# MRCS-Morse-Code-Buzzer.net
KiCad netlist of a schematic drawn in EAGLE
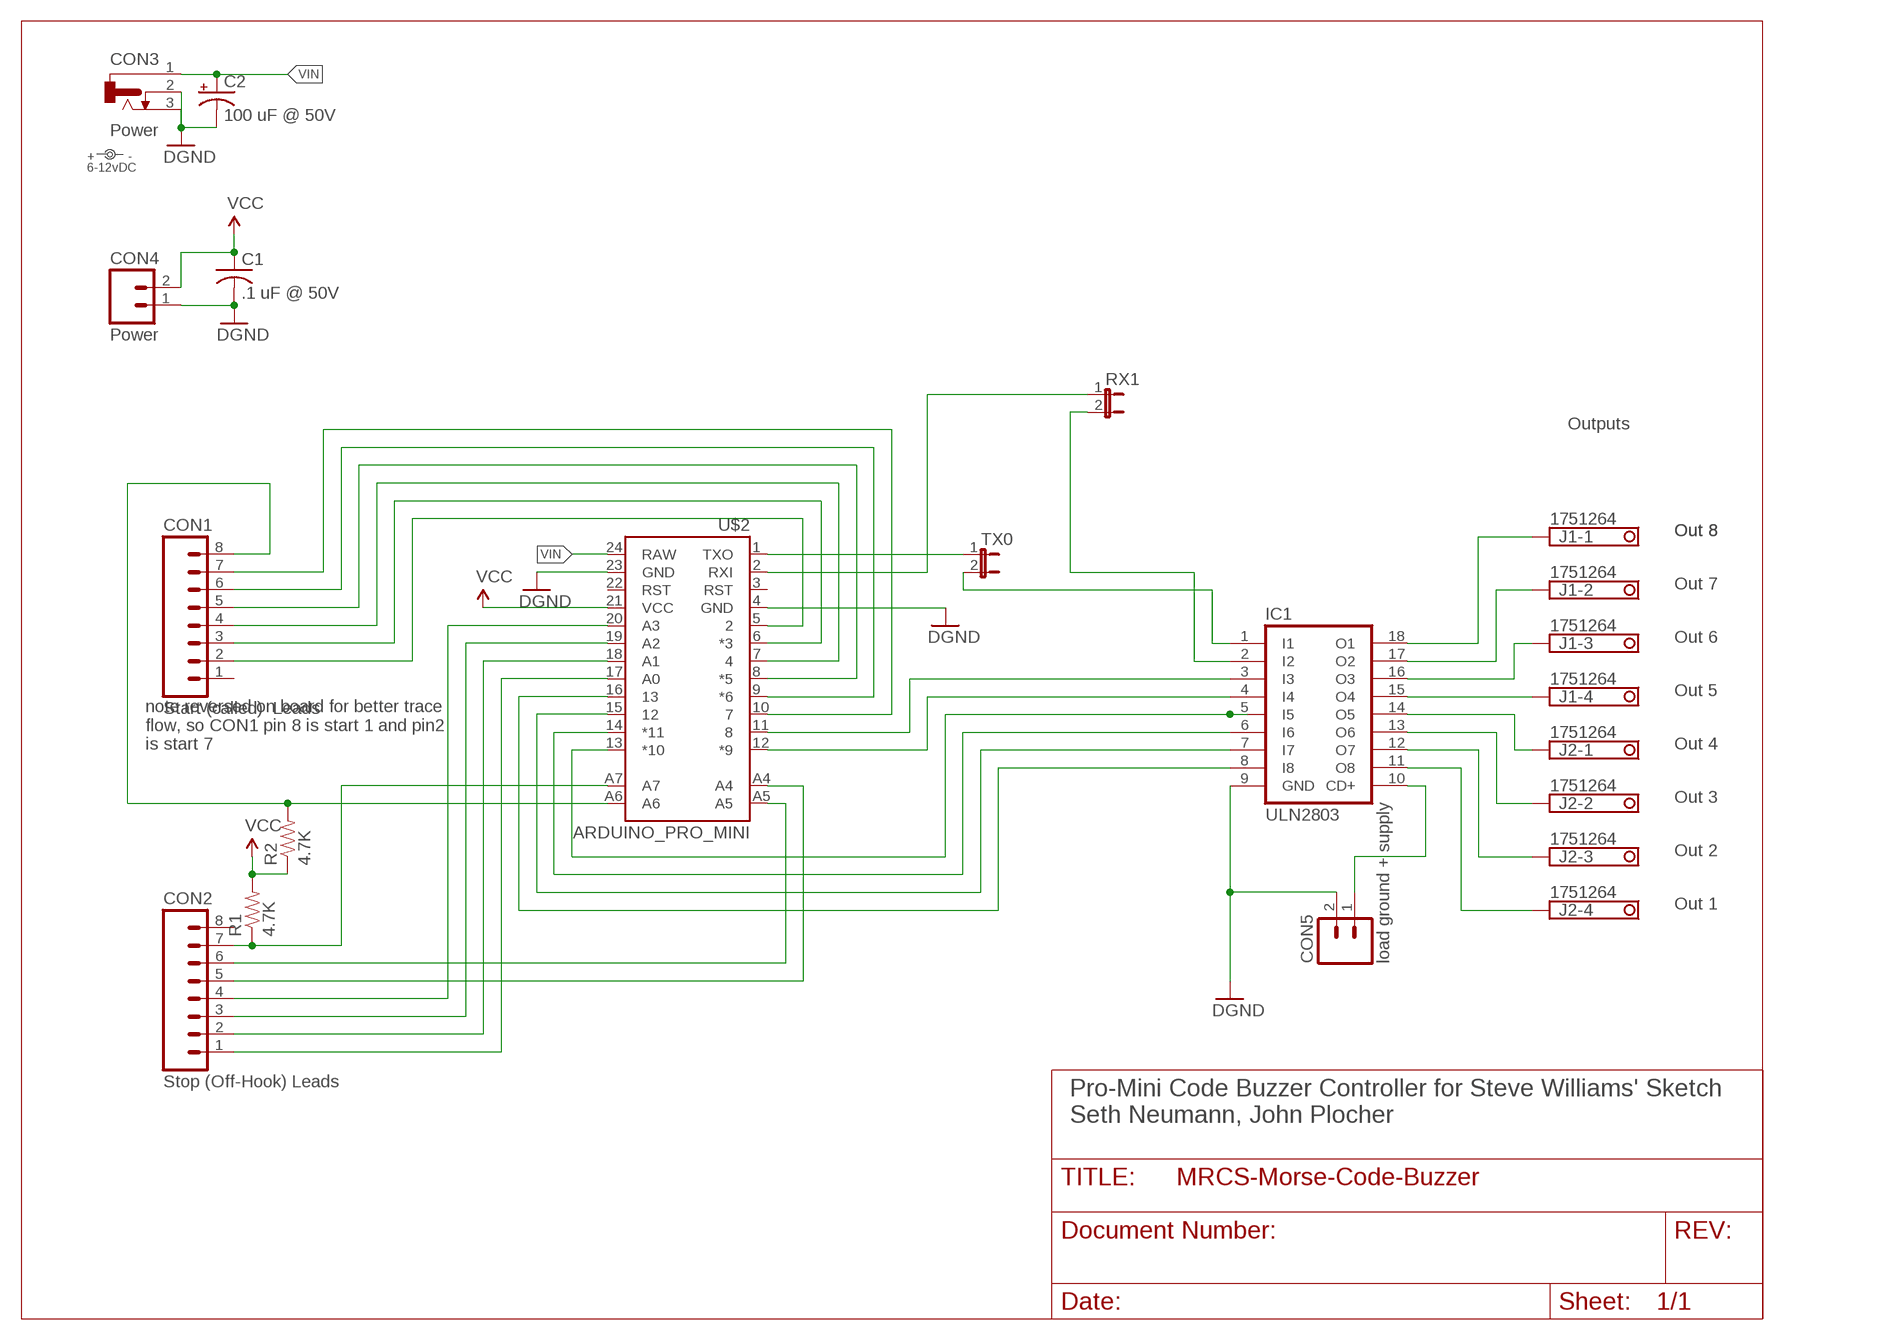
[diagram p0: schematic, sheet 1]

(export (version "E")
  (design (tool "Eeschema 10.0.6"))
  (components
    (comp (ref "C1")
      (value ".1 uF @ 50V")
      (footprint "eagle-import:C025-030X050")
      (libsource (lib "eagle-import") (part "C-US025-030X050"))
    )
    (comp (ref "C2")
      (value "100 uF @ 50V")
      (footprint "eagle-import:E3.5-10")
      (libsource (lib "eagle-import") (part "CAP-POLPTH-3.5MM"))
    )
    (comp (ref "CON1")
      (value "Start (called) Leads")
      (footprint "eagle-import:1X08_LOCK")
      (libsource (lib "eagle-import") (part "CONNECTOR-M08LOCK"))
    )
    (comp (ref "CON2")
      (value "Stop (Off-Hook) Leads")
      (footprint "eagle-import:1X08_LOCK")
      (libsource (lib "eagle-import") (part "CONNECTOR-M08LOCK"))
    )
    (comp (ref "CON3")
      (value "Power")
      (footprint "eagle-import:DCJ0202")
      (libsource (lib "eagle-import") (part "CONNECTOR-DC-POWER-RA"))
    )
    (comp (ref "CON4")
      (value "Power")
      (footprint "eagle-import:MSTB2")
      (libsource (lib "eagle-import") (part "CONNECTOR-M02508-LOCK"))
    )
    (comp (ref "CON5")
      (value "load ground + supply")
      (footprint "eagle-import:MSTB2")
      (libsource (lib "eagle-import") (part "CONNECTOR-M02508-LOCK"))
    )
    (comp (ref "IC1")
      (value "ULN2803")
      (footprint "eagle-import:DIL18")
      (libsource (lib "eagle-import") (part "ULN2803A"))
    )
    (comp (ref "J1")
      (value "1751264")
      (footprint "eagle-import:1751264")
      (libsource (lib "eagle-import") (part "1751264"))
    )
    (comp (ref "J2")
      (value "1751264")
      (footprint "eagle-import:1751264")
      (libsource (lib "eagle-import") (part "1751264"))
    )
    (comp (ref "R1")
      (value "4.7K")
      (footprint "eagle-import:AXIAL-0.4-RES")
      (libsource (lib "eagle-import") (part "RPTH04"))
    )
    (comp (ref "R2")
      (value "4.7K")
      (footprint "eagle-import:AXIAL-0.4-RES")
      (libsource (lib "eagle-import") (part "RPTH04"))
    )
    (comp (ref "RX1")
      (value "JUMPER-2PTH")
      (footprint "eagle-import:1X02")
      (libsource (lib "eagle-import") (part "JUMPER-2PTH"))
    )
    (comp (ref "TX0")
      (value "JUMPER-2PTH")
      (footprint "eagle-import:1X02")
      (libsource (lib "eagle-import") (part "JUMPER-2PTH"))
    )
    (comp (ref "U$2")
      (value "ARDUINO_PRO_MINI")
      (footprint "eagle-import:ARDUINO_PRO_MINI")
      (libsource (lib "eagle-import") (part "ARDUINO_PRO_MINI"))
    )
    (comp (ref "U$4")
      (value "6-12vDC")
      (footprint "eagle-import:PWR_LABEL")
      (libsource (lib "eagle-import") (part "DOC-POWER_LABEL"))
    )
  )
  (nets
    (net (code "1") (name "DGND") (class "Default")
      (node (ref "C1") (pin "2") (pinfunction "2_2") (pintype "passive"))
      (node (ref "C2") (pin "-") (pinfunction "-_-") (pintype "passive"))
      (node (ref "CON3") (pin "2") (pinfunction "2_2") (pintype "passive"))
      (node (ref "CON3") (pin "3") (pinfunction "3_3") (pintype "passive"))
      (node (ref "CON4") (pin "1") (pinfunction "A_1") (pintype "passive"))
      (node (ref "CON5") (pin "2") (pinfunction "B_2") (pintype "passive"))
      (node (ref "IC1") (pin "9") (pinfunction "GND_9") (pintype "power_in"))
      (node (ref "U$2") (pin "23") (pinfunction "GND_23") (pintype "bidirectional"))
      (node (ref "U$2") (pin "4") (pinfunction "GND_4") (pintype "bidirectional"))
    )
    (net (code "2") (name "Net-(CON2-Pad5)") (class "Default")
      (node (ref "CON2") (pin "5") (pinfunction "5_5") (pintype "passive"))
      (node (ref "U$2") (pin "A4") (pinfunction "A4_A4") (pintype "bidirectional"))
    )
    (net (code "3") (name "Net-(CON2-Pad6)") (class "Default")
      (node (ref "CON2") (pin "6") (pinfunction "6_6") (pintype "passive"))
      (node (ref "U$2") (pin "A5") (pinfunction "A5_A5") (pintype "bidirectional"))
    )
    (net (code "4") (name "Net-(CON5-A)") (class "Default")
      (node (ref "CON5") (pin "1") (pinfunction "A_1") (pintype "passive"))
      (node (ref "IC1") (pin "10") (pinfunction "CD+_10") (pintype "passive"))
    )
    (net (code "5") (name "Net-(IC1-I1)") (class "Default")
      (node (ref "IC1") (pin "1") (pinfunction "I1_1") (pintype "input"))
      (node (ref "TX0") (pin "2") (pinfunction "2_2") (pintype "passive"))
    )
    (net (code "6") (name "Net-(IC1-I2)") (class "Default")
      (node (ref "IC1") (pin "2") (pinfunction "I2_2") (pintype "input"))
      (node (ref "RX1") (pin "2") (pinfunction "2_2") (pintype "passive"))
    )
    (net (code "7") (name "Net-(IC1-I3)") (class "Default")
      (node (ref "IC1") (pin "3") (pinfunction "I3_3") (pintype "input"))
      (node (ref "U$2") (pin "11") (pinfunction "8_11") (pintype "bidirectional"))
    )
    (net (code "8") (name "Net-(IC1-I4)") (class "Default")
      (node (ref "IC1") (pin "4") (pinfunction "I4_4") (pintype "input"))
      (node (ref "U$2") (pin "12") (pinfunction "*9_12") (pintype "bidirectional"))
    )
    (net (code "9") (name "Net-(IC1-I5)") (class "Default")
      (node (ref "IC1") (pin "5") (pinfunction "I5_5") (pintype "input"))
      (node (ref "U$2") (pin "13") (pinfunction "*10_13") (pintype "bidirectional"))
    )
    (net (code "10") (name "Net-(IC1-I6)") (class "Default")
      (node (ref "IC1") (pin "6") (pinfunction "I6_6") (pintype "input"))
      (node (ref "U$2") (pin "14") (pinfunction "*11_14") (pintype "bidirectional"))
    )
    (net (code "11") (name "Net-(IC1-I7)") (class "Default")
      (node (ref "IC1") (pin "7") (pinfunction "I7_7") (pintype "input"))
      (node (ref "U$2") (pin "15") (pinfunction "12_15") (pintype "bidirectional"))
    )
    (net (code "12") (name "Net-(IC1-I8)") (class "Default")
      (node (ref "IC1") (pin "8") (pinfunction "I8_8") (pintype "input"))
      (node (ref "U$2") (pin "16") (pinfunction "13_16") (pintype "bidirectional"))
    )
    (net (code "13") (name "Net-(IC1-O1)") (class "Default")
      (node (ref "IC1") (pin "18") (pinfunction "O1_18") (pintype "open_collector"))
      (node (ref "J1") (pin "1") (pinfunction "K_1") (pintype "passive"))
    )
    (net (code "14") (name "Net-(IC1-O2)") (class "Default")
      (node (ref "IC1") (pin "17") (pinfunction "O2_17") (pintype "open_collector"))
      (node (ref "J1") (pin "2") (pinfunction "K_2") (pintype "passive"))
    )
    (net (code "15") (name "Net-(IC1-O3)") (class "Default")
      (node (ref "IC1") (pin "16") (pinfunction "O3_16") (pintype "open_collector"))
      (node (ref "J1") (pin "3") (pinfunction "K_3") (pintype "passive"))
    )
    (net (code "16") (name "Net-(IC1-O4)") (class "Default")
      (node (ref "IC1") (pin "15") (pinfunction "O4_15") (pintype "open_collector"))
      (node (ref "J1") (pin "4") (pinfunction "K_4") (pintype "passive"))
    )
    (net (code "17") (name "Net-(IC1-O5)") (class "Default")
      (node (ref "IC1") (pin "14") (pinfunction "O5_14") (pintype "open_collector"))
      (node (ref "J2") (pin "1") (pinfunction "K_1") (pintype "passive"))
    )
    (net (code "18") (name "Net-(IC1-O6)") (class "Default")
      (node (ref "IC1") (pin "13") (pinfunction "O6_13") (pintype "open_collector"))
      (node (ref "J2") (pin "2") (pinfunction "K_2") (pintype "passive"))
    )
    (net (code "19") (name "Net-(IC1-O7)") (class "Default")
      (node (ref "IC1") (pin "12") (pinfunction "O7_12") (pintype "open_collector"))
      (node (ref "J2") (pin "3") (pinfunction "K_3") (pintype "passive"))
    )
    (net (code "20") (name "Net-(IC1-O8)") (class "Default")
      (node (ref "IC1") (pin "11") (pinfunction "O8_11") (pintype "open_collector"))
      (node (ref "J2") (pin "4") (pinfunction "K_4") (pintype "passive"))
    )
    (net (code "21") (name "Net-(R1-1)") (class "Default")
      (node (ref "CON2") (pin "7") (pinfunction "7_7") (pintype "passive"))
      (node (ref "R1") (pin "P$1") (pinfunction "1_P$1") (pintype "passive"))
      (node (ref "U$2") (pin "A7") (pinfunction "A7_A7") (pintype "bidirectional"))
    )
    (net (code "22") (name "Net-(R2-2)") (class "Default")
      (node (ref "CON1") (pin "8") (pinfunction "8_8") (pintype "passive"))
      (node (ref "R2") (pin "P$2") (pinfunction "2_P$2") (pintype "passive"))
      (node (ref "U$2") (pin "A6") (pinfunction "A6_A6") (pintype "bidirectional"))
    )
    (net (code "23") (name "Net-(U$2-*3)") (class "Default")
      (node (ref "CON1") (pin "3") (pinfunction "3_3") (pintype "passive"))
      (node (ref "U$2") (pin "6") (pinfunction "*3_6") (pintype "bidirectional"))
    )
    (net (code "24") (name "Net-(U$2-*5)") (class "Default")
      (node (ref "CON1") (pin "5") (pinfunction "5_5") (pintype "passive"))
      (node (ref "U$2") (pin "8") (pinfunction "*5_8") (pintype "bidirectional"))
    )
    (net (code "25") (name "Net-(U$2-*6)") (class "Default")
      (node (ref "CON1") (pin "6") (pinfunction "6_6") (pintype "passive"))
      (node (ref "U$2") (pin "9") (pinfunction "*6_9") (pintype "bidirectional"))
    )
    (net (code "26") (name "Net-(U$2-2)") (class "Default")
      (node (ref "CON1") (pin "2") (pinfunction "2_2") (pintype "passive"))
      (node (ref "U$2") (pin "5") (pinfunction "2_5") (pintype "bidirectional"))
    )
    (net (code "27") (name "Net-(U$2-4)") (class "Default")
      (node (ref "CON1") (pin "4") (pinfunction "4_4") (pintype "passive"))
      (node (ref "U$2") (pin "7") (pinfunction "4_7") (pintype "bidirectional"))
    )
    (net (code "28") (name "Net-(U$2-7)") (class "Default")
      (node (ref "CON1") (pin "7") (pinfunction "7_7") (pintype "passive"))
      (node (ref "U$2") (pin "10") (pinfunction "7_10") (pintype "bidirectional"))
    )
    (net (code "29") (name "Net-(U$2-A0)") (class "Default")
      (node (ref "CON2") (pin "1") (pinfunction "1_1") (pintype "passive"))
      (node (ref "U$2") (pin "17") (pinfunction "A0_17") (pintype "bidirectional"))
    )
    (net (code "30") (name "Net-(U$2-A1)") (class "Default")
      (node (ref "CON2") (pin "2") (pinfunction "2_2") (pintype "passive"))
      (node (ref "U$2") (pin "18") (pinfunction "A1_18") (pintype "bidirectional"))
    )
    (net (code "31") (name "Net-(U$2-A2)") (class "Default")
      (node (ref "CON2") (pin "3") (pinfunction "3_3") (pintype "passive"))
      (node (ref "U$2") (pin "19") (pinfunction "A2_19") (pintype "bidirectional"))
    )
    (net (code "32") (name "Net-(U$2-A3)") (class "Default")
      (node (ref "CON2") (pin "4") (pinfunction "4_4") (pintype "passive"))
      (node (ref "U$2") (pin "20") (pinfunction "A3_20") (pintype "bidirectional"))
    )
    (net (code "33") (name "Net-(U$2-RXI)") (class "Default")
      (node (ref "RX1") (pin "1") (pinfunction "1_1") (pintype "passive"))
      (node (ref "U$2") (pin "2") (pinfunction "RXI_2") (pintype "bidirectional"))
    )
    (net (code "34") (name "Net-(U$2-TXO)") (class "Default")
      (node (ref "TX0") (pin "1") (pinfunction "1_1") (pintype "passive"))
      (node (ref "U$2") (pin "1") (pinfunction "TXO_1") (pintype "bidirectional"))
    )
    (net (code "35") (name "VCC") (class "Default")
      (node (ref "C1") (pin "1") (pinfunction "1_1") (pintype "passive"))
      (node (ref "CON4") (pin "2") (pinfunction "B_2") (pintype "passive"))
      (node (ref "R1") (pin "P$2") (pinfunction "2_P$2") (pintype "passive"))
      (node (ref "R2") (pin "P$1") (pinfunction "1_P$1") (pintype "passive"))
      (node (ref "U$2") (pin "21") (pinfunction "VCC_21") (pintype "bidirectional"))
    )
    (net (code "36") (name "VIN") (class "Default")
      (node (ref "C2") (pin "+") (pinfunction "+_+") (pintype "passive"))
      (node (ref "CON3") (pin "1") (pinfunction "1_1") (pintype "passive"))
      (node (ref "U$2") (pin "24") (pinfunction "RAW_24") (pintype "bidirectional"))
    )
    (net (code "37") (name "unconnected-(CON1-Pad1)") (class "Default")
      (node (ref "CON1") (pin "1") (pinfunction "1_1") (pintype "passive"))
    )
    (net (code "38") (name "unconnected-(CON2-Pad8)") (class "Default")
      (node (ref "CON2") (pin "8") (pinfunction "8_8") (pintype "passive"))
    )
    (net (code "39") (name "unconnected-(U$2-RST-Pad3)") (class "Default")
      (node (ref "U$2") (pin "3") (pinfunction "RST_3") (pintype "bidirectional"))
    )
    (net (code "40") (name "unconnected-(U$2-RST-Pad22)") (class "Default")
      (node (ref "U$2") (pin "22") (pinfunction "RST_22") (pintype "bidirectional"))
    )
  )
)
